# STM32.net
KiCad netlist of a schematic drawn in Altium Designer
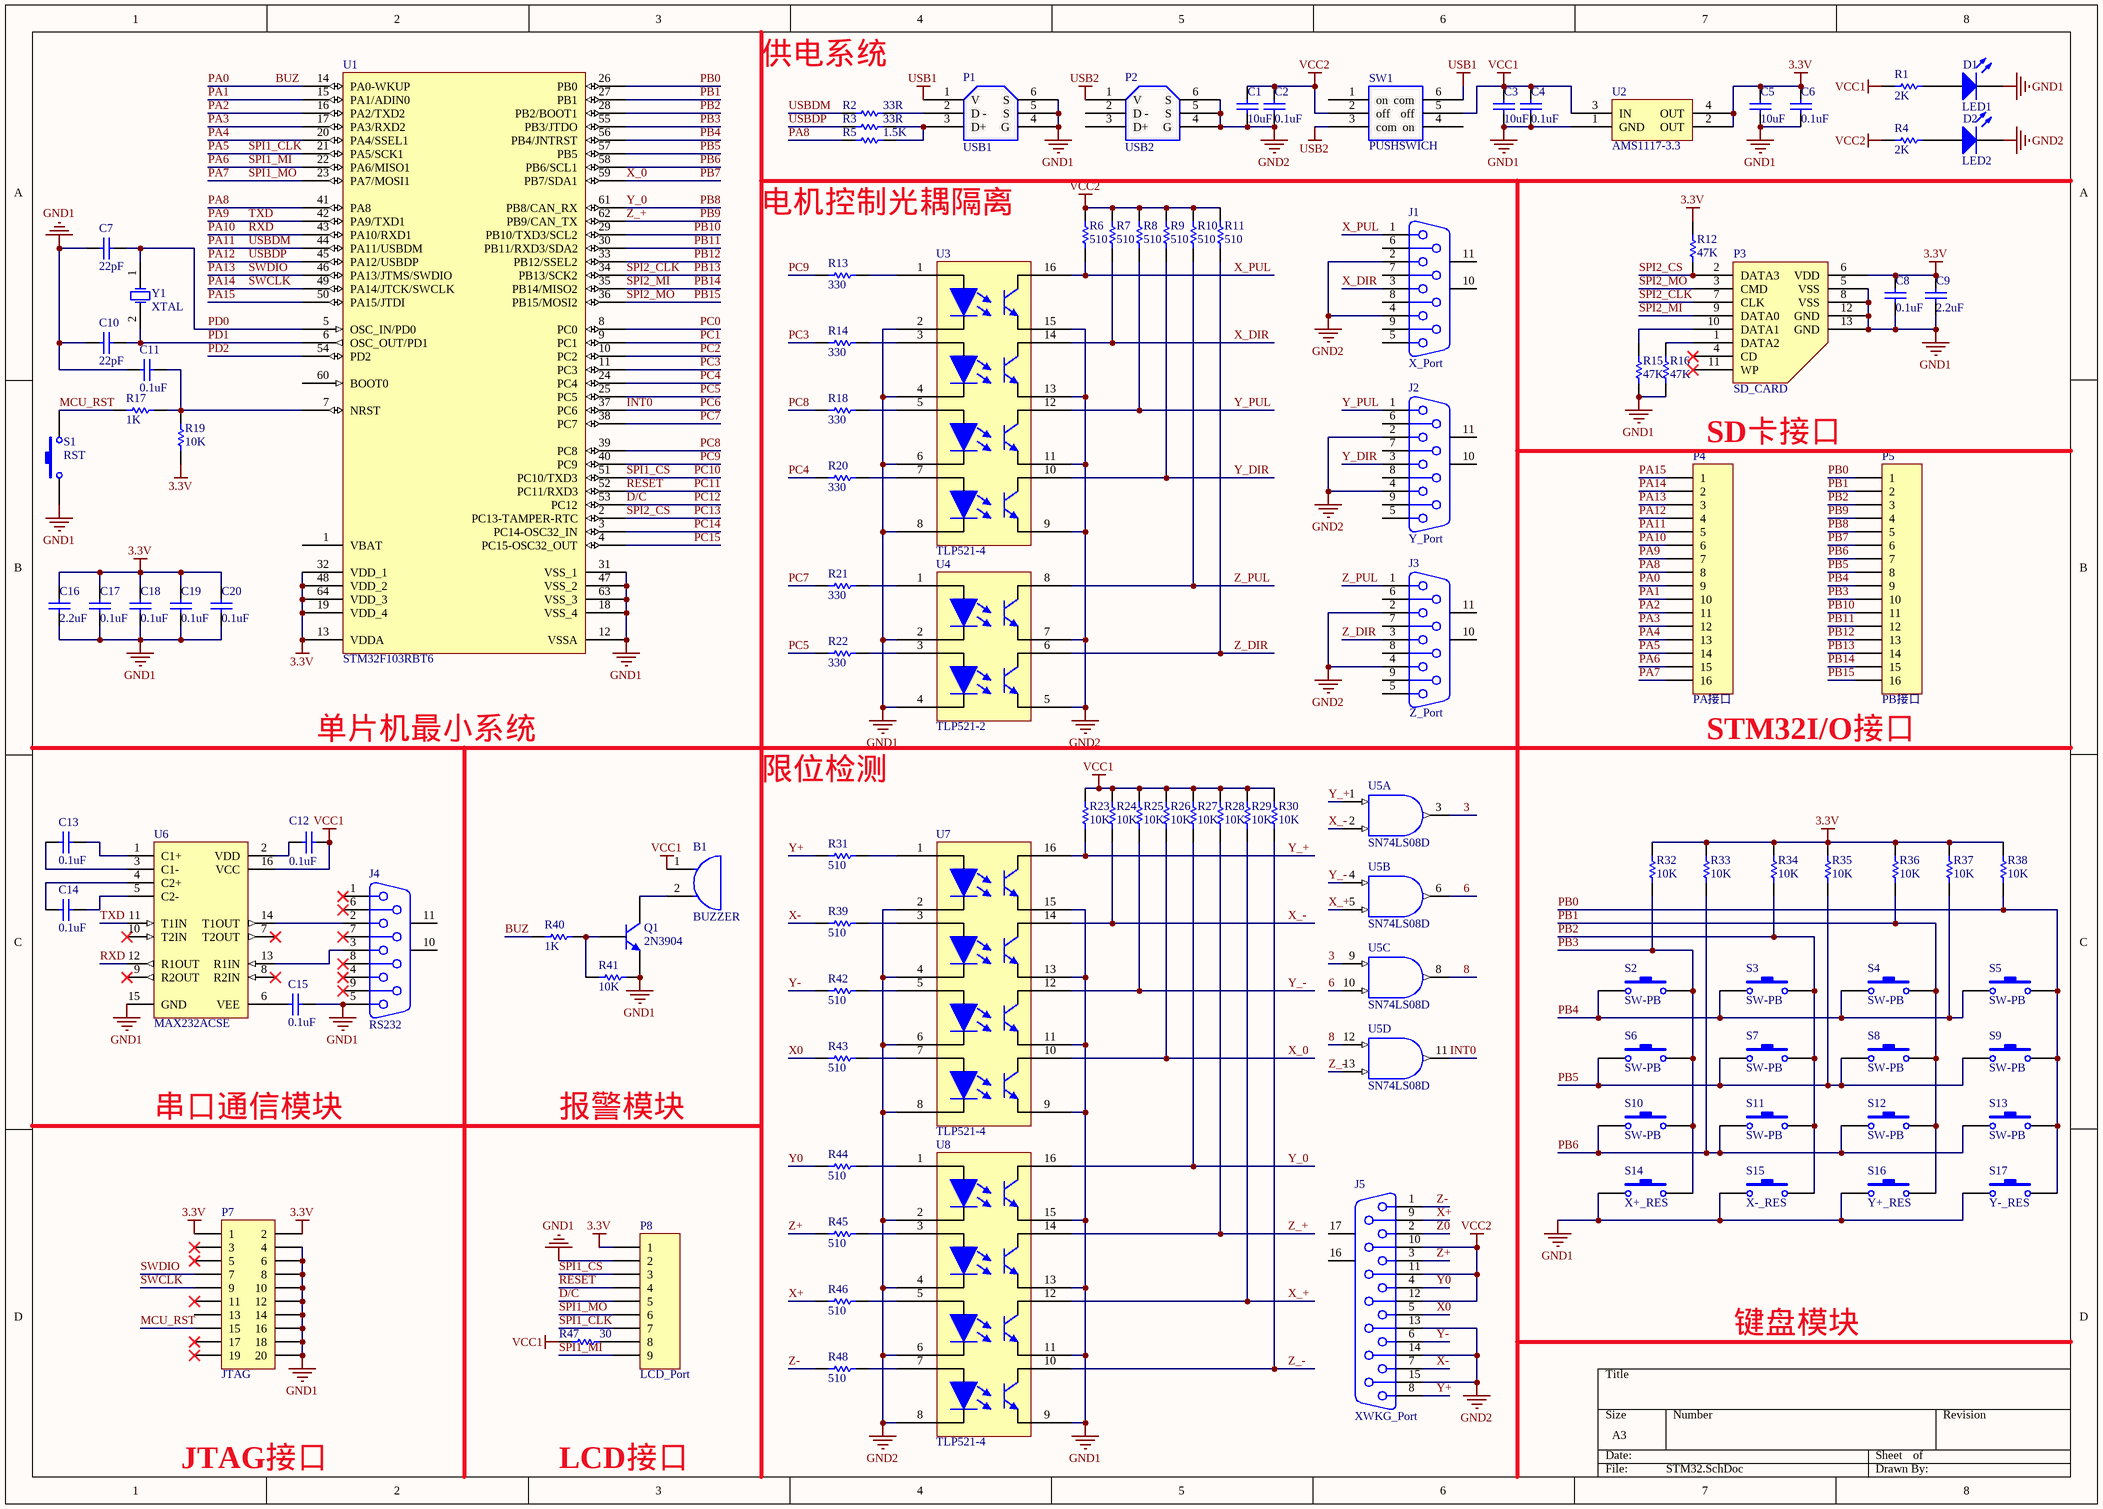
[diagram p0: STM32.SchDoc]

(export (version "E")
  (design (tool "Eeschema 10.0.6"))
  (components
    (comp (ref "B1")
      (value "BUZZER")
      (footprint "BUZZER")
      (description "Buzzer")
      (libsource (lib "Miscellaneous Devices") (part "BUZZER"))
    )
    (comp (ref "C1")
      (value "10uF")
      (footprint "0805")
      (description "Capacitor")
      (fields (field (name "Comment") "Cap") (field (name "PUBLISHER") "Altium Limited"))
      (libsource (lib "Miscellaneous Devices") (part "Cap"))
    )
    (comp (ref "C2")
      (value "0.1uF")
      (footprint "0805")
      (description "Capacitor")
      (fields (field (name "Comment") "Cap") (field (name "PUBLISHER") "Altium Limited"))
      (libsource (lib "Miscellaneous Devices") (part "Cap"))
    )
    (comp (ref "C3")
      (value "10uF")
      (footprint "0805")
      (description "Capacitor")
      (fields (field (name "Comment") "Cap") (field (name "PUBLISHER") "Altium Limited"))
      (libsource (lib "Miscellaneous Devices") (part "Cap"))
    )
    (comp (ref "C4")
      (value "0.1uF")
      (footprint "0805")
      (description "Capacitor")
      (fields (field (name "Comment") "Cap") (field (name "PUBLISHER") "Altium Limited"))
      (libsource (lib "Miscellaneous Devices") (part "Cap"))
    )
    (comp (ref "C5")
      (value "10uF")
      (footprint "0805")
      (description "Capacitor")
      (fields (field (name "Comment") "Cap") (field (name "PUBLISHER") "Altium Limited"))
      (libsource (lib "Miscellaneous Devices") (part "Cap"))
    )
    (comp (ref "C6")
      (value "0.1uF")
      (footprint "0805")
      (description "Capacitor")
      (fields (field (name "Comment") "Cap") (field (name "PUBLISHER") "Altium Limited"))
      (libsource (lib "Miscellaneous Devices") (part "Cap"))
    )
    (comp (ref "C7")
      (value "22pF")
      (footprint "0805")
      (description "Capacitor")
      (fields (field (name "Comment") "Cap") (field (name "PUBLISHER") "Altium Limited"))
      (libsource (lib "Miscellaneous Devices") (part "Cap"))
    )
    (comp (ref "C8")
      (value "0.1uF")
      (footprint "0805")
      (description "Capacitor")
      (fields (field (name "Comment") "Cap") (field (name "PUBLISHER") "Altium Limited"))
      (libsource (lib "Miscellaneous Devices") (part "Cap"))
    )
    (comp (ref "C9")
      (value "2.2uF")
      (footprint "0805")
      (description "Capacitor")
      (fields (field (name "Comment") "Cap") (field (name "PUBLISHER") "Altium Limited"))
      (libsource (lib "Miscellaneous Devices") (part "Cap"))
    )
    (comp (ref "C10")
      (value "22pF")
      (footprint "0805")
      (description "Capacitor")
      (fields (field (name "Comment") "Cap") (field (name "PUBLISHER") "Altium Limited"))
      (libsource (lib "Miscellaneous Devices") (part "Cap"))
    )
    (comp (ref "C11")
      (value "0.1uF")
      (footprint "0805")
      (description "Capacitor")
      (fields (field (name "Comment") "Cap") (field (name "PUBLISHER") "Altium Limited"))
      (libsource (lib "Miscellaneous Devices") (part "Cap"))
    )
    (comp (ref "C12")
      (value "0.1uF")
      (footprint "0805")
      (description "Capacitor")
      (fields (field (name "Comment") "Cap") (field (name "PUBLISHER") "Altium Limited"))
      (libsource (lib "Miscellaneous Devices") (part "Cap"))
    )
    (comp (ref "C13")
      (value "0.1uF")
      (footprint "0805")
      (description "Capacitor")
      (fields (field (name "Comment") "Cap") (field (name "PUBLISHER") "Altium Limited"))
      (libsource (lib "Miscellaneous Devices") (part "Cap"))
    )
    (comp (ref "C14")
      (value "0.1uF")
      (footprint "0805")
      (description "Capacitor")
      (fields (field (name "Comment") "Cap") (field (name "PUBLISHER") "Altium Limited"))
      (libsource (lib "Miscellaneous Devices") (part "Cap"))
    )
    (comp (ref "C15")
      (value "0.1uF")
      (footprint "0805")
      (description "Capacitor")
      (fields (field (name "Comment") "Cap") (field (name "PUBLISHER") "Altium Limited"))
      (libsource (lib "Miscellaneous Devices") (part "Cap"))
    )
    (comp (ref "C16")
      (value "2.2uF")
      (footprint "ShiPeng:0805")
      (description "Capacitor")
      (fields (field (name "Comment") "Cap") (field (name "PUBLISHER") "Altium Limited"))
      (libsource (lib "Miscellaneous Devices") (part "Cap"))
    )
    (comp (ref "C17")
      (value "0.1uF")
      (footprint "ShiPeng:0805")
      (description "Capacitor")
      (fields (field (name "Comment") "Cap") (field (name "PUBLISHER") "Altium Limited"))
      (libsource (lib "Miscellaneous Devices") (part "Cap"))
    )
    (comp (ref "C18")
      (value "0.1uF")
      (footprint "ShiPeng:0805")
      (description "Capacitor")
      (fields (field (name "Comment") "Cap") (field (name "PUBLISHER") "Altium Limited"))
      (libsource (lib "Miscellaneous Devices") (part "Cap"))
    )
    (comp (ref "C19")
      (value "0.1uF")
      (footprint "ShiPeng:0805")
      (description "Capacitor")
      (fields (field (name "Comment") "Cap") (field (name "PUBLISHER") "Altium Limited"))
      (libsource (lib "Miscellaneous Devices") (part "Cap"))
    )
    (comp (ref "C20")
      (value "0.1uF")
      (footprint "ShiPeng:0805")
      (description "Capacitor")
      (fields (field (name "Comment") "Cap") (field (name "PUBLISHER") "Altium Limited"))
      (libsource (lib "Miscellaneous Devices") (part "Cap"))
    )
    (comp (ref "D1")
      (value "LED1")
      (footprint "0805")
      (description "Typical INFRARED GaAs LED")
      (fields (field (name "PUBLISHER") "Altium Limited"))
      (libsource (lib "Miscellaneous Devices") (part "LED0"))
    )
    (comp (ref "D2")
      (value "LED2")
      (footprint "0805")
      (description "Typical INFRARED GaAs LED")
      (fields (field (name "PUBLISHER") "Altium Limited"))
      (libsource (lib "Miscellaneous Devices") (part "LED0"))
    )
    (comp (ref "J1")
      (value "X_Port")
      (footprint "DSUB1.385-2H9")
      (description "Receptacle Assembly, 9 Position, Right Angle")
      (fields (field (name "PUBLISHER") "Altium Limited"))
      (libsource (lib "Miscellaneous Connectors") (part "D Connector 9"))
    )
    (comp (ref "J2")
      (value "Y_Port")
      (footprint "DSUB1.385-2H9")
      (description "Receptacle Assembly, 9 Position, Right Angle")
      (fields (field (name "PUBLISHER") "Altium Limited"))
      (libsource (lib "Miscellaneous Connectors") (part "D Connector 9"))
    )
    (comp (ref "J3")
      (value "Z_Port")
      (footprint "DSUB1.385-2H9")
      (description "Receptacle Assembly, 9 Position, Right Angle")
      (fields (field (name "PUBLISHER") "Altium Limited"))
      (libsource (lib "Miscellaneous Connectors") (part "D Connector 9"))
    )
    (comp (ref "J4")
      (value "RS232")
      (footprint "DSUB1.385-2H9")
      (description "Receptacle Assembly, 9 Position, Right Angle")
      (fields (field (name "PUBLISHER") "Altium Limited"))
      (libsource (lib "Miscellaneous Connectors") (part "D Connector 9"))
    )
    (comp (ref "J5")
      (value "XWKG_Port")
      (footprint "DSUB1.385-2H15")
      (description "Receptacle Assembly, 15 Position, Right Angle")
      (fields (field (name "PUBLISHER") "Altium Limited"))
      (libsource (lib "Miscellaneous Connectors") (part "D Connector 15"))
    )
    (comp (ref "P1") (value "USB1") (footprint "ShiPeng:USB") (libsource (lib "*") (part "USB")))
    (comp (ref "P2") (value "USB2") (footprint "ShiPeng:USB") (libsource (lib "*") (part "USB")))
    (comp (ref "P3") (value "SD_CARD") (footprint "SD_CARD") (libsource (lib "ShiPeng") (part "SD_CARD")))
    (comp (ref "P4")
      (value "PA接口")
      (footprint "HDR1X16")
      (description "Header, 16-Pin")
      (fields (field (name "PUBLISHER") "Altium Limited"))
      (libsource (lib "Miscellaneous Connectors") (part "Header 16"))
    )
    (comp (ref "P5")
      (value "PB接口")
      (footprint "HDR1X16")
      (description "Header, 16-Pin")
      (fields (field (name "PUBLISHER") "Altium Limited"))
      (libsource (lib "Miscellaneous Connectors") (part "Header 16"))
    )
    (comp (ref "P7")
      (value "JTAG")
      (footprint "ShiPeng:JTAG")
      (description "Header, 10-Pin, Dual row")
      (fields (field (name "PUBLISHER") "Altium Limited"))
      (libsource (lib "Miscellaneous Connectors") (part "Header 10X2"))
    )
    (comp (ref "P8")
      (value "LCD_Port")
      (footprint "HDR1X9")
      (description "Header, 9-Pin")
      (fields (field (name "PUBLISHER") "Altium Limited"))
      (libsource (lib "Miscellaneous Connectors") (part "Header 9"))
    )
    (comp (ref "Q1")
      (value "2N3904")
      (footprint "TO-92A")
      (description "NPN General Purpose Amplifier")
      (fields (field (name "PUBLISHER") "Altium Limited"))
      (libsource (lib "Miscellaneous Devices") (part "2N3904"))
    )
    (comp (ref "R1")
      (value "2K")
      (footprint "0805")
      (description "Semiconductor Resistor")
      (fields (field (name "PUBLISHER") "Altium Limited"))
      (libsource (lib "Miscellaneous Devices") (part "Res Semi"))
    )
    (comp (ref "R2")
      (value "33R")
      (footprint "0805")
      (description "Semiconductor Resistor")
      (fields (field (name "PUBLISHER") "Altium Limited"))
      (libsource (lib "Miscellaneous Devices") (part "Res Semi"))
    )
    (comp (ref "R3")
      (value "33R")
      (footprint "0805")
      (description "Semiconductor Resistor")
      (fields (field (name "PUBLISHER") "Altium Limited"))
      (libsource (lib "Miscellaneous Devices") (part "Res Semi"))
    )
    (comp (ref "R4")
      (value "2K")
      (footprint "0805")
      (description "Semiconductor Resistor")
      (fields (field (name "PUBLISHER") "Altium Limited"))
      (libsource (lib "Miscellaneous Devices") (part "Res Semi"))
    )
    (comp (ref "R5")
      (value "1.5K")
      (footprint "0805")
      (description "Semiconductor Resistor")
      (fields (field (name "PUBLISHER") "Altium Limited"))
      (libsource (lib "Miscellaneous Devices") (part "Res Semi"))
    )
    (comp (ref "R6")
      (value "510")
      (footprint "0805")
      (description "Semiconductor Resistor")
      (fields (field (name "PUBLISHER") "Altium Limited"))
      (libsource (lib "Miscellaneous Devices") (part "Res Semi"))
    )
    (comp (ref "R7")
      (value "510")
      (footprint "ShiPeng:0805")
      (description "Semiconductor Resistor")
      (fields (field (name "PUBLISHER") "Altium Limited"))
      (libsource (lib "Miscellaneous Devices") (part "Res Semi"))
    )
    (comp (ref "R8")
      (value "510")
      (footprint "ShiPeng:0805")
      (description "Semiconductor Resistor")
      (fields (field (name "PUBLISHER") "Altium Limited"))
      (libsource (lib "Miscellaneous Devices") (part "Res Semi"))
    )
    (comp (ref "R9")
      (value "510")
      (footprint "ShiPeng:0805")
      (description "Semiconductor Resistor")
      (fields (field (name "PUBLISHER") "Altium Limited"))
      (libsource (lib "Miscellaneous Devices") (part "Res Semi"))
    )
    (comp (ref "R10")
      (value "510")
      (footprint "ShiPeng:0805")
      (description "Semiconductor Resistor")
      (fields (field (name "PUBLISHER") "Altium Limited"))
      (libsource (lib "Miscellaneous Devices") (part "Res Semi"))
    )
    (comp (ref "R11")
      (value "510")
      (footprint "ShiPeng:0805")
      (description "Semiconductor Resistor")
      (fields (field (name "PUBLISHER") "Altium Limited"))
      (libsource (lib "Miscellaneous Devices") (part "Res Semi"))
    )
    (comp (ref "R12")
      (value "47K")
      (footprint "0805")
      (description "Semiconductor Resistor")
      (fields (field (name "PUBLISHER") "Altium Limited"))
      (libsource (lib "Miscellaneous Devices") (part "Res Semi"))
    )
    (comp (ref "R13")
      (value "330")
      (footprint "ShiPeng:0805")
      (description "Semiconductor Resistor")
      (fields (field (name "PUBLISHER") "Altium Limited"))
      (libsource (lib "Miscellaneous Devices") (part "Res Semi"))
    )
    (comp (ref "R14")
      (value "330")
      (footprint "ShiPeng:0805")
      (description "Semiconductor Resistor")
      (fields (field (name "PUBLISHER") "Altium Limited"))
      (libsource (lib "Miscellaneous Devices") (part "Res Semi"))
    )
    (comp (ref "R15")
      (value "47K")
      (footprint "ShiPeng:0805")
      (description "Semiconductor Resistor")
      (fields (field (name "PUBLISHER") "Altium Limited"))
      (libsource (lib "Miscellaneous Devices") (part "Res Semi"))
    )
    (comp (ref "R16")
      (value "47K")
      (footprint "0805")
      (description "Semiconductor Resistor")
      (fields (field (name "PUBLISHER") "Altium Limited"))
      (libsource (lib "Miscellaneous Devices") (part "Res Semi"))
    )
    (comp (ref "R17")
      (value "1K")
      (footprint "ShiPeng:0805")
      (description "Semiconductor Resistor")
      (fields (field (name "PUBLISHER") "Altium Limited"))
      (libsource (lib "Miscellaneous Devices") (part "Res Semi"))
    )
    (comp (ref "R18")
      (value "330")
      (footprint "ShiPeng:0805")
      (description "Semiconductor Resistor")
      (fields (field (name "PUBLISHER") "Altium Limited"))
      (libsource (lib "Miscellaneous Devices") (part "Res Semi"))
    )
    (comp (ref "R19")
      (value "10K")
      (footprint "ShiPeng:0805")
      (description "Semiconductor Resistor")
      (fields (field (name "PUBLISHER") "Altium Limited"))
      (libsource (lib "Miscellaneous Devices") (part "Res Semi"))
    )
    (comp (ref "R20")
      (value "330")
      (footprint "ShiPeng:0805")
      (description "Semiconductor Resistor")
      (fields (field (name "PUBLISHER") "Altium Limited"))
      (libsource (lib "Miscellaneous Devices") (part "Res Semi"))
    )
    (comp (ref "R21")
      (value "330")
      (footprint "0805")
      (description "Semiconductor Resistor")
      (fields (field (name "PUBLISHER") "Altium Limited"))
      (libsource (lib "Miscellaneous Devices") (part "Res Semi"))
    )
    (comp (ref "R22")
      (value "330")
      (footprint "ShiPeng:0805")
      (description "Semiconductor Resistor")
      (fields (field (name "PUBLISHER") "Altium Limited"))
      (libsource (lib "Miscellaneous Devices") (part "Res Semi"))
    )
    (comp (ref "R23")
      (value "10K")
      (footprint "ShiPeng:0805")
      (description "Semiconductor Resistor")
      (fields (field (name "PUBLISHER") "Altium Limited"))
      (libsource (lib "Miscellaneous Devices") (part "Res Semi"))
    )
    (comp (ref "R24")
      (value "10K")
      (footprint "ShiPeng:0805")
      (description "Semiconductor Resistor")
      (fields (field (name "PUBLISHER") "Altium Limited"))
      (libsource (lib "Miscellaneous Devices") (part "Res Semi"))
    )
    (comp (ref "R25")
      (value "10K")
      (footprint "ShiPeng:0805")
      (description "Semiconductor Resistor")
      (fields (field (name "PUBLISHER") "Altium Limited"))
      (libsource (lib "Miscellaneous Devices") (part "Res Semi"))
    )
    (comp (ref "R26")
      (value "10K")
      (footprint "ShiPeng:0805")
      (description "Semiconductor Resistor")
      (fields (field (name "PUBLISHER") "Altium Limited"))
      (libsource (lib "Miscellaneous Devices") (part "Res Semi"))
    )
    (comp (ref "R27")
      (value "10K")
      (footprint "ShiPeng:0805")
      (description "Semiconductor Resistor")
      (fields (field (name "PUBLISHER") "Altium Limited"))
      (libsource (lib "Miscellaneous Devices") (part "Res Semi"))
    )
    (comp (ref "R28")
      (value "10K")
      (footprint "ShiPeng:0805")
      (description "Semiconductor Resistor")
      (fields (field (name "PUBLISHER") "Altium Limited"))
      (libsource (lib "Miscellaneous Devices") (part "Res Semi"))
    )
    (comp (ref "R29")
      (value "10K")
      (footprint "ShiPeng:0805")
      (description "Semiconductor Resistor")
      (fields (field (name "PUBLISHER") "Altium Limited"))
      (libsource (lib "Miscellaneous Devices") (part "Res Semi"))
    )
    (comp (ref "R30")
      (value "10K")
      (footprint "ShiPeng:0805")
      (description "Semiconductor Resistor")
      (fields (field (name "PUBLISHER") "Altium Limited"))
      (libsource (lib "Miscellaneous Devices") (part "Res Semi"))
    )
    (comp (ref "R31")
      (value "510")
      (footprint "ShiPeng:0805")
      (description "Semiconductor Resistor")
      (fields (field (name "PUBLISHER") "Altium Limited"))
      (libsource (lib "Miscellaneous Devices") (part "Res Semi"))
    )
    (comp (ref "R32")
      (value "10K")
      (footprint "ShiPeng:0805")
      (description "Semiconductor Resistor")
      (fields (field (name "PUBLISHER") "Altium Limited"))
      (libsource (lib "Miscellaneous Devices") (part "Res Semi"))
    )
    (comp (ref "R33")
      (value "10K")
      (footprint "ShiPeng:0805")
      (description "Semiconductor Resistor")
      (fields (field (name "PUBLISHER") "Altium Limited"))
      (libsource (lib "Miscellaneous Devices") (part "Res Semi"))
    )
    (comp (ref "R34")
      (value "10K")
      (footprint "ShiPeng:0805")
      (description "Semiconductor Resistor")
      (fields (field (name "PUBLISHER") "Altium Limited"))
      (libsource (lib "Miscellaneous Devices") (part "Res Semi"))
    )
    (comp (ref "R35")
      (value "10K")
      (footprint "0805")
      (description "Semiconductor Resistor")
      (fields (field (name "PUBLISHER") "Altium Limited"))
      (libsource (lib "Miscellaneous Devices") (part "Res Semi"))
    )
    (comp (ref "R36")
      (value "10K")
      (footprint "ShiPeng:0805")
      (description "Semiconductor Resistor")
      (fields (field (name "PUBLISHER") "Altium Limited"))
      (libsource (lib "Miscellaneous Devices") (part "Res Semi"))
    )
    (comp (ref "R37")
      (value "10K")
      (footprint "ShiPeng:0805")
      (description "Semiconductor Resistor")
      (fields (field (name "PUBLISHER") "Altium Limited"))
      (libsource (lib "Miscellaneous Devices") (part "Res Semi"))
    )
    (comp (ref "R38")
      (value "10K")
      (footprint "ShiPeng:0805")
      (description "Semiconductor Resistor")
      (fields (field (name "PUBLISHER") "Altium Limited"))
      (libsource (lib "Miscellaneous Devices") (part "Res Semi"))
    )
    (comp (ref "R39")
      (value "510")
      (footprint "ShiPeng:0805")
      (description "Semiconductor Resistor")
      (fields (field (name "PUBLISHER") "Altium Limited"))
      (libsource (lib "Miscellaneous Devices") (part "Res Semi"))
    )
    (comp (ref "R40")
      (value "1K")
      (footprint "ShiPeng:0805")
      (description "Semiconductor Resistor")
      (fields (field (name "PUBLISHER") "Altium Limited"))
      (libsource (lib "Miscellaneous Devices") (part "Res Semi"))
    )
    (comp (ref "R41")
      (value "10K")
      (footprint "ShiPeng:0805")
      (description "Semiconductor Resistor")
      (fields (field (name "PUBLISHER") "Altium Limited"))
      (libsource (lib "Miscellaneous Devices") (part "Res Semi"))
    )
    (comp (ref "R42")
      (value "510")
      (footprint "ShiPeng:0805")
      (description "Semiconductor Resistor")
      (fields (field (name "PUBLISHER") "Altium Limited"))
      (libsource (lib "Miscellaneous Devices") (part "Res Semi"))
    )
    (comp (ref "R43")
      (value "510")
      (footprint "ShiPeng:0805")
      (description "Semiconductor Resistor")
      (fields (field (name "PUBLISHER") "Altium Limited"))
      (libsource (lib "Miscellaneous Devices") (part "Res Semi"))
    )
    (comp (ref "R44")
      (value "510")
      (footprint "ShiPeng:0805")
      (description "Semiconductor Resistor")
      (fields (field (name "PUBLISHER") "Altium Limited"))
      (libsource (lib "Miscellaneous Devices") (part "Res Semi"))
    )
    (comp (ref "R45")
      (value "510")
      (footprint "ShiPeng:0805")
      (description "Semiconductor Resistor")
      (fields (field (name "PUBLISHER") "Altium Limited"))
      (libsource (lib "Miscellaneous Devices") (part "Res Semi"))
    )
    (comp (ref "R46")
      (value "510")
      (footprint "ShiPeng:0805")
      (description "Semiconductor Resistor")
      (fields (field (name "PUBLISHER") "Altium Limited"))
      (libsource (lib "Miscellaneous Devices") (part "Res Semi"))
    )
    (comp (ref "R47")
      (value "30")
      (footprint "ShiPeng:0805")
      (description "Semiconductor Resistor")
      (fields (field (name "PUBLISHER") "Altium Limited"))
      (libsource (lib "Miscellaneous Devices") (part "Res Semi"))
    )
    (comp (ref "R48")
      (value "510")
      (footprint "ShiPeng:0805")
      (description "Semiconductor Resistor")
      (fields (field (name "PUBLISHER") "Altium Limited"))
      (libsource (lib "Miscellaneous Devices") (part "Res Semi"))
    )
    (comp (ref "S1")
      (value "RST")
      (footprint "SW-PB")
      (description "Switch")
      (fields (field (name "PUBLISHER") "Altium Limited"))
      (libsource (lib "Miscellaneous Devices") (part "SW-PB"))
    )
    (comp (ref "S2")
      (value "SW-PB")
      (footprint "SW-PB")
      (description "Switch")
      (fields (field (name "PUBLISHER") "Altium Limited"))
      (libsource (lib "Miscellaneous Devices") (part "SW-PB"))
    )
    (comp (ref "S3")
      (value "SW-PB")
      (footprint "SW-PB")
      (description "Switch")
      (fields (field (name "PUBLISHER") "Altium Limited"))
      (libsource (lib "Miscellaneous Devices") (part "SW-PB"))
    )
    (comp (ref "S4")
      (value "SW-PB")
      (footprint "SW-PB")
      (description "Switch")
      (fields (field (name "PUBLISHER") "Altium Limited"))
      (libsource (lib "Miscellaneous Devices") (part "SW-PB"))
    )
    (comp (ref "S5")
      (value "SW-PB")
      (footprint "SW-PB")
      (description "Switch")
      (fields (field (name "PUBLISHER") "Altium Limited"))
      (libsource (lib "Miscellaneous Devices") (part "SW-PB"))
    )
    (comp (ref "S6")
      (value "SW-PB")
      (footprint "SW-PB")
      (description "Switch")
      (fields (field (name "PUBLISHER") "Altium Limited"))
      (libsource (lib "Miscellaneous Devices") (part "SW-PB"))
    )
    (comp (ref "S7")
      (value "SW-PB")
      (footprint "SW-PB")
      (description "Switch")
      (fields (field (name "PUBLISHER") "Altium Limited"))
      (libsource (lib "Miscellaneous Devices") (part "SW-PB"))
    )
    (comp (ref "S8")
      (value "SW-PB")
      (footprint "SW-PB")
      (description "Switch")
      (fields (field (name "PUBLISHER") "Altium Limited"))
      (libsource (lib "Miscellaneous Devices") (part "SW-PB"))
    )
    (comp (ref "S9")
      (value "SW-PB")
      (footprint "SW-PB")
      (description "Switch")
      (fields (field (name "PUBLISHER") "Altium Limited"))
      (libsource (lib "Miscellaneous Devices") (part "SW-PB"))
    )
    (comp (ref "S10")
      (value "SW-PB")
      (footprint "SW-PB")
      (description "Switch")
      (fields (field (name "PUBLISHER") "Altium Limited"))
      (libsource (lib "Miscellaneous Devices") (part "SW-PB"))
    )
    (comp (ref "S11")
      (value "SW-PB")
      (footprint "SW-PB")
      (description "Switch")
      (fields (field (name "PUBLISHER") "Altium Limited"))
      (libsource (lib "Miscellaneous Devices") (part "SW-PB"))
    )
    (comp (ref "S12")
      (value "SW-PB")
      (footprint "SW-PB")
      (description "Switch")
      (fields (field (name "PUBLISHER") "Altium Limited"))
      (libsource (lib "Miscellaneous Devices") (part "SW-PB"))
    )
    (comp (ref "S13")
      (value "SW-PB")
      (footprint "SW-PB")
      (description "Switch")
      (fields (field (name "PUBLISHER") "Altium Limited"))
      (libsource (lib "Miscellaneous Devices") (part "SW-PB"))
    )
    (comp (ref "S14")
      (value "X+_RES")
      (footprint "SW-PB")
      (description "Switch")
      (fields (field (name "PUBLISHER") "Altium Limited"))
      (libsource (lib "Miscellaneous Devices") (part "SW-PB"))
    )
    (comp (ref "S15")
      (value "X-_RES")
      (footprint "SW-PB")
      (description "Switch")
      (fields (field (name "PUBLISHER") "Altium Limited"))
      (libsource (lib "Miscellaneous Devices") (part "SW-PB"))
    )
    (comp (ref "S16")
      (value "Y+_RES")
      (footprint "SW-PB")
      (description "Switch")
      (fields (field (name "PUBLISHER") "Altium Limited"))
      (libsource (lib "Miscellaneous Devices") (part "SW-PB"))
    )
    (comp (ref "S17")
      (value "Y-_RES")
      (footprint "SW-PB")
      (description "Switch")
      (fields (field (name "PUBLISHER") "Altium Limited"))
      (libsource (lib "Miscellaneous Devices") (part "SW-PB"))
    )
    (comp (ref "SW1")
      (value "PUSHSWICH")
      (footprint "ShiPeng:DPDT-6")
      (libsource (lib "ShiPeng") (part "PUSHSWICH"))
    )
    (comp (ref "U1")
      (value "STM32F103RBT6")
      (footprint "ShiPeng:LQFP64_L")
      (libsource (lib "ShiPeng") (part "STM32F103RBT6"))
    )
    (comp (ref "U2")
      (value "AMS1117-3.3")
      (footprint "ShiPeng:SOT223")
      (libsource (lib "ShiPeng") (part "AMS1117-3.3"))
    )
    (comp (ref "U3")
      (value "TLP521-4")
      (footprint "Miscellaneous Devices:DIP-16")
      (libsource (lib "ShiPeng") (part "TLP521-4"))
    )
    (comp (ref "U4")
      (value "TLP521-2")
      (footprint "Miscellaneous Devices:DIP-8")
      (libsource (lib "ShiPeng") (part "TLP521-2"))
    )
    (comp (ref "U5")
      (value "SN74LS08D")
      (footprint "ShiPeng:D014_N")
      (description "Quadruple 2-Input Positive-AND Gate")
      (fields (field (name "PUBLISHER") "Altium Limited"))
      (libsource (lib "TI Logic Gate 2") (part "SN74LS08D"))
    )
    (comp (ref "U6")
      (value "MAX232ACSE")
      (footprint "NSO16_N")
      (description "+5V Powered, Multi-Channel RS-232 Driver/Receiver")
      (fields (field (name "PUBLISHER") "Altium Limited"))
      (libsource (lib "Maxim Communication Transceiver") (part "MAX232ACSE"))
    )
    (comp (ref "U7")
      (value "TLP521-4")
      (footprint "Miscellaneous Devices:DIP-16")
      (libsource (lib "ShiPeng") (part "TLP521-4"))
    )
    (comp (ref "U8")
      (value "TLP521-4")
      (footprint "Miscellaneous Devices:DIP-16")
      (libsource (lib "ShiPeng") (part "TLP521-4"))
    )
    (comp (ref "Y1")
      (value "XTAL")
      (footprint "ShiPeng:JZ")
      (description "Crystal Oscillator")
      (fields (field (name "PUBLISHER") "Altium Limited"))
      (libsource (lib "Miscellaneous Devices") (part "XTAL"))
    )
  )
  (nets
    (net (code "1") (name "/3") (class "Default")
      (node (ref "U5") (pin "3") (pinfunction "Y_3") (pintype "output"))
      (node (ref "U5") (pin "9") (pinfunction "A_9") (pintype "input"))
    )
    (net (code "2") (name "/6") (class "Default")
      (node (ref "U5") (pin "10") (pinfunction "B_10") (pintype "input"))
      (node (ref "U5") (pin "6") (pinfunction "Y_6") (pintype "output"))
    )
    (net (code "3") (name "/8") (class "Default")
      (node (ref "U5") (pin "12") (pinfunction "A_12") (pintype "input"))
      (node (ref "U5") (pin "8") (pinfunction "Y_8") (pintype "output"))
    )
    (net (code "4") (name "/BUZ") (class "Default")
      (node (ref "P4") (pin "9") (pinfunction "9_9") (pintype "passive"))
      (node (ref "R40") (pin "1") (pinfunction "1_1") (pintype "passive"))
      (node (ref "U1") (pin "14") (pinfunction "PA0-WKUP_14") (pintype "bidirectional"))
    )
    (net (code "5") (name "/D{slash}C") (class "Default")
      (node (ref "P8") (pin "5") (pinfunction "5_5") (pintype "passive"))
      (node (ref "U1") (pin "53") (pinfunction "PC12_53") (pintype "bidirectional"))
    )
    (net (code "6") (name "/INT0") (class "Default")
      (node (ref "U1") (pin "37") (pinfunction "PC6_37") (pintype "bidirectional"))
      (node (ref "U5") (pin "11") (pinfunction "Y_11") (pintype "output"))
    )
    (net (code "7") (name "/MCU_RST") (class "Default")
      (node (ref "P7") (pin "15") (pinfunction "15_15") (pintype "passive"))
      (node (ref "R17") (pin "2") (pinfunction "2_2") (pintype "passive"))
      (node (ref "S1") (pin "2") (pinfunction "2_2") (pintype "passive"))
    )
    (net (code "8") (name "/PA1") (class "Default")
      (node (ref "P4") (pin "10") (pinfunction "10_10") (pintype "passive"))
      (node (ref "U1") (pin "15") (pinfunction "PA1/ADIN0_15") (pintype "bidirectional"))
    )
    (net (code "9") (name "/PA2") (class "Default")
      (node (ref "P4") (pin "11") (pinfunction "11_11") (pintype "passive"))
      (node (ref "U1") (pin "16") (pinfunction "PA2/TXD2_16") (pintype "bidirectional"))
    )
    (net (code "10") (name "/PA3") (class "Default")
      (node (ref "P4") (pin "12") (pinfunction "12_12") (pintype "passive"))
      (node (ref "U1") (pin "17") (pinfunction "PA3/RXD2_17") (pintype "bidirectional"))
    )
    (net (code "11") (name "/PA4") (class "Default")
      (node (ref "P4") (pin "13") (pinfunction "13_13") (pintype "passive"))
      (node (ref "U1") (pin "20") (pinfunction "PA4/SSEL1_20") (pintype "bidirectional"))
    )
    (net (code "12") (name "/PA5") (class "Default")
      (node (ref "P4") (pin "14") (pinfunction "14_14") (pintype "passive"))
      (node (ref "P8") (pin "7") (pinfunction "7_7") (pintype "passive"))
      (node (ref "U1") (pin "21") (pinfunction "PA5/SCK1_21") (pintype "bidirectional"))
    )
    (net (code "13") (name "/PA6") (class "Default")
      (node (ref "P4") (pin "15") (pinfunction "15_15") (pintype "passive"))
      (node (ref "P8") (pin "9") (pinfunction "9_9") (pintype "passive"))
      (node (ref "U1") (pin "22") (pinfunction "PA6/MISO1_22") (pintype "bidirectional"))
    )
    (net (code "14") (name "/PA7") (class "Default")
      (node (ref "P4") (pin "16") (pinfunction "16_16") (pintype "passive"))
      (node (ref "P8") (pin "6") (pinfunction "6_6") (pintype "passive"))
      (node (ref "U1") (pin "23") (pinfunction "PA7/MOSI1_23") (pintype "bidirectional"))
    )
    (net (code "15") (name "/PA8") (class "Default")
      (node (ref "P4") (pin "8") (pinfunction "8_8") (pintype "passive"))
      (node (ref "R5") (pin "1") (pinfunction "1_1") (pintype "passive"))
      (node (ref "U1") (pin "41") (pinfunction "PA8_41") (pintype "bidirectional"))
    )
    (net (code "16") (name "/PA9") (class "Default")
      (node (ref "P4") (pin "7") (pinfunction "7_7") (pintype "passive"))
      (node (ref "U1") (pin "42") (pinfunction "PA9/TXD1_42") (pintype "bidirectional"))
      (node (ref "U6") (pin "11") (pinfunction "T1IN_11") (pintype "input"))
    )
    (net (code "17") (name "/PA10") (class "Default")
      (node (ref "P4") (pin "6") (pinfunction "6_6") (pintype "passive"))
      (node (ref "U1") (pin "43") (pinfunction "PA10/RXD1_43") (pintype "bidirectional"))
      (node (ref "U6") (pin "12") (pinfunction "R1OUT_12") (pintype "output"))
    )
    (net (code "18") (name "/PA11") (class "Default")
      (node (ref "P4") (pin "5") (pinfunction "5_5") (pintype "passive"))
      (node (ref "R2") (pin "1") (pinfunction "1_1") (pintype "passive"))
      (node (ref "U1") (pin "44") (pinfunction "PA11/USBDM_44") (pintype "bidirectional"))
    )
    (net (code "19") (name "/PA12") (class "Default")
      (node (ref "P4") (pin "4") (pinfunction "4_4") (pintype "passive"))
      (node (ref "R3") (pin "1") (pinfunction "1_1") (pintype "passive"))
      (node (ref "U1") (pin "45") (pinfunction "PA12/USBDP_45") (pintype "bidirectional"))
    )
    (net (code "20") (name "/PA13") (class "Default")
      (node (ref "P4") (pin "3") (pinfunction "3_3") (pintype "passive"))
      (node (ref "P7") (pin "7") (pinfunction "7_7") (pintype "passive"))
      (node (ref "U1") (pin "46") (pinfunction "PA13/JTMS/SWDIO_46") (pintype "bidirectional"))
    )
    (net (code "21") (name "/PA14") (class "Default")
      (node (ref "P4") (pin "2") (pinfunction "2_2") (pintype "passive"))
      (node (ref "P7") (pin "9") (pinfunction "9_9") (pintype "passive"))
      (node (ref "U1") (pin "49") (pinfunction "PA14/JTCK/SWCLK_49") (pintype "bidirectional"))
    )
    (net (code "22") (name "/PA15") (class "Default")
      (node (ref "P4") (pin "1") (pinfunction "1_1") (pintype "passive"))
      (node (ref "U1") (pin "50") (pinfunction "PA15/JTDI_50") (pintype "bidirectional"))
    )
    (net (code "23") (name "/PB0") (class "Default")
      (node (ref "P5") (pin "1") (pinfunction "1_1") (pintype "passive"))
      (node (ref "R38") (pin "2") (pinfunction "2_2") (pintype "passive"))
      (node (ref "S13") (pin "2") (pinfunction "2_2") (pintype "passive"))
      (node (ref "S17") (pin "2") (pinfunction "2_2") (pintype "passive"))
      (node (ref "S5") (pin "2") (pinfunction "2_2") (pintype "passive"))
      (node (ref "S9") (pin "2") (pinfunction "2_2") (pintype "passive"))
      (node (ref "U1") (pin "26") (pinfunction "PB0_26") (pintype "bidirectional"))
    )
    (net (code "24") (name "/PB1") (class "Default")
      (node (ref "P5") (pin "2") (pinfunction "2_2") (pintype "passive"))
      (node (ref "R36") (pin "2") (pinfunction "2_2") (pintype "passive"))
      (node (ref "S12") (pin "2") (pinfunction "2_2") (pintype "passive"))
      (node (ref "S16") (pin "2") (pinfunction "2_2") (pintype "passive"))
      (node (ref "S4") (pin "2") (pinfunction "2_2") (pintype "passive"))
      (node (ref "S8") (pin "2") (pinfunction "2_2") (pintype "passive"))
      (node (ref "U1") (pin "27") (pinfunction "PB1_27") (pintype "bidirectional"))
    )
    (net (code "25") (name "/PB2") (class "Default")
      (node (ref "P5") (pin "3") (pinfunction "3_3") (pintype "passive"))
      (node (ref "R34") (pin "2") (pinfunction "2_2") (pintype "passive"))
      (node (ref "S11") (pin "2") (pinfunction "2_2") (pintype "passive"))
      (node (ref "S15") (pin "2") (pinfunction "2_2") (pintype "passive"))
      (node (ref "S3") (pin "2") (pinfunction "2_2") (pintype "passive"))
      (node (ref "S7") (pin "2") (pinfunction "2_2") (pintype "passive"))
      (node (ref "U1") (pin "28") (pinfunction "PB2/BOOT1_28") (pintype "bidirectional"))
    )
    (net (code "26") (name "/PB3") (class "Default")
      (node (ref "P5") (pin "10") (pinfunction "10_10") (pintype "passive"))
      (node (ref "R32") (pin "2") (pinfunction "2_2") (pintype "passive"))
      (node (ref "S10") (pin "2") (pinfunction "2_2") (pintype "passive"))
      (node (ref "S14") (pin "2") (pinfunction "2_2") (pintype "passive"))
      (node (ref "S2") (pin "2") (pinfunction "2_2") (pintype "passive"))
      (node (ref "S6") (pin "2") (pinfunction "2_2") (pintype "passive"))
      (node (ref "U1") (pin "55") (pinfunction "PB3/JTDO_55") (pintype "bidirectional"))
    )
    (net (code "27") (name "/PB4") (class "Default")
      (node (ref "P5") (pin "9") (pinfunction "9_9") (pintype "passive"))
      (node (ref "R37") (pin "2") (pinfunction "2_2") (pintype "passive"))
      (node (ref "S2") (pin "1") (pinfunction "1_1") (pintype "passive"))
      (node (ref "S3") (pin "1") (pinfunction "1_1") (pintype "passive"))
      (node (ref "S4") (pin "1") (pinfunction "1_1") (pintype "passive"))
      (node (ref "S5") (pin "1") (pinfunction "1_1") (pintype "passive"))
      (node (ref "U1") (pin "56") (pinfunction "PB4/JNTRST_56") (pintype "bidirectional"))
    )
    (net (code "28") (name "/PB5") (class "Default")
      (node (ref "P5") (pin "8") (pinfunction "8_8") (pintype "passive"))
      (node (ref "R35") (pin "2") (pinfunction "2_2") (pintype "passive"))
      (node (ref "S6") (pin "1") (pinfunction "1_1") (pintype "passive"))
      (node (ref "S7") (pin "1") (pinfunction "1_1") (pintype "passive"))
      (node (ref "S8") (pin "1") (pinfunction "1_1") (pintype "passive"))
      (node (ref "S9") (pin "1") (pinfunction "1_1") (pintype "passive"))
      (node (ref "U1") (pin "57") (pinfunction "PB5_57") (pintype "bidirectional"))
    )
    (net (code "29") (name "/PB6") (class "Default")
      (node (ref "P5") (pin "7") (pinfunction "7_7") (pintype "passive"))
      (node (ref "R33") (pin "2") (pinfunction "2_2") (pintype "passive"))
      (node (ref "S10") (pin "1") (pinfunction "1_1") (pintype "passive"))
      (node (ref "S11") (pin "1") (pinfunction "1_1") (pintype "passive"))
      (node (ref "S12") (pin "1") (pinfunction "1_1") (pintype "passive"))
      (node (ref "S13") (pin "1") (pinfunction "1_1") (pintype "passive"))
      (node (ref "U1") (pin "58") (pinfunction "PB6/SCL1_58") (pintype "bidirectional"))
    )
    (net (code "30") (name "/PB7") (class "Default")
      (node (ref "P5") (pin "6") (pinfunction "6_6") (pintype "passive"))
      (node (ref "R26") (pin "2") (pinfunction "2_2") (pintype "passive"))
      (node (ref "U1") (pin "59") (pinfunction "PB7/SDA1_59") (pintype "bidirectional"))
      (node (ref "U7") (pin "10") (pintype "passive"))
    )
    (net (code "31") (name "/PB8") (class "Default")
      (node (ref "P5") (pin "5") (pinfunction "5_5") (pintype "passive"))
      (node (ref "R27") (pin "2") (pinfunction "2_2") (pintype "passive"))
      (node (ref "U1") (pin "61") (pinfunction "PB8/CAN_RX_61") (pintype "bidirectional"))
      (node (ref "U8") (pin "16") (pintype "passive"))
    )
    (net (code "32") (name "/PB9") (class "Default")
      (node (ref "P5") (pin "4") (pinfunction "4_4") (pintype "passive"))
      (node (ref "R28") (pin "2") (pinfunction "2_2") (pintype "passive"))
      (node (ref "U1") (pin "62") (pinfunction "PB9/CAN_TX_62") (pintype "bidirectional"))
      (node (ref "U8") (pin "14") (pintype "passive"))
    )
    (net (code "33") (name "/PB10") (class "Default")
      (node (ref "P5") (pin "11") (pinfunction "11_11") (pintype "passive"))
      (node (ref "U1") (pin "29") (pinfunction "PB10/TXD3/SCL2_29") (pintype "bidirectional"))
    )
    (net (code "34") (name "/PB11") (class "Default")
      (node (ref "P5") (pin "12") (pinfunction "12_12") (pintype "passive"))
      (node (ref "U1") (pin "30") (pinfunction "PB11/RXD3/SDA2_30") (pintype "bidirectional"))
    )
    (net (code "35") (name "/PB12") (class "Default")
      (node (ref "P5") (pin "13") (pinfunction "13_13") (pintype "passive"))
      (node (ref "U1") (pin "33") (pinfunction "PB12/SSEL2_33") (pintype "bidirectional"))
    )
    (net (code "36") (name "/PB13") (class "Default")
      (node (ref "P3") (pin "7") (pinfunction "CLK_7") (pintype "passive"))
      (node (ref "P5") (pin "14") (pinfunction "14_14") (pintype "passive"))
      (node (ref "U1") (pin "34") (pinfunction "PB13/SCK2_34") (pintype "bidirectional"))
    )
    (net (code "37") (name "/PB14") (class "Default")
      (node (ref "P3") (pin "9") (pinfunction "DATA0_9") (pintype "passive"))
      (node (ref "P5") (pin "15") (pinfunction "15_15") (pintype "passive"))
      (node (ref "U1") (pin "35") (pinfunction "PB14/MISO2_35") (pintype "bidirectional"))
    )
    (net (code "38") (name "/PB15") (class "Default")
      (node (ref "P3") (pin "3") (pinfunction "CMD_3") (pintype "passive"))
      (node (ref "P5") (pin "16") (pinfunction "16_16") (pintype "passive"))
      (node (ref "U1") (pin "36") (pinfunction "PB15/MOSI2_36") (pintype "bidirectional"))
    )
    (net (code "39") (name "/PC0") (class "Default")
      (node (ref "U1") (pin "8") (pinfunction "PC0_8") (pintype "bidirectional"))
    )
    (net (code "40") (name "/PC1") (class "Default")
      (node (ref "U1") (pin "9") (pinfunction "PC1_9") (pintype "bidirectional"))
    )
    (net (code "41") (name "/PC2") (class "Default")
      (node (ref "U1") (pin "10") (pinfunction "PC2_10") (pintype "bidirectional"))
    )
    (net (code "42") (name "/PC3") (class "Default")
      (node (ref "R14") (pin "2") (pinfunction "2_2") (pintype "passive"))
      (node (ref "U1") (pin "11") (pinfunction "PC3_11") (pintype "bidirectional"))
    )
    (net (code "43") (name "/PC4") (class "Default")
      (node (ref "R20") (pin "2") (pinfunction "2_2") (pintype "passive"))
      (node (ref "U1") (pin "24") (pinfunction "PC4_24") (pintype "bidirectional"))
    )
    (net (code "44") (name "/PC5") (class "Default")
      (node (ref "R22") (pin "2") (pinfunction "2_2") (pintype "passive"))
      (node (ref "U1") (pin "25") (pinfunction "PC5_25") (pintype "bidirectional"))
    )
    (net (code "45") (name "/PC7") (class "Default")
      (node (ref "R21") (pin "2") (pinfunction "2_2") (pintype "passive"))
      (node (ref "U1") (pin "38") (pinfunction "PC7_38") (pintype "bidirectional"))
    )
    (net (code "46") (name "/PC8") (class "Default")
      (node (ref "R18") (pin "2") (pinfunction "2_2") (pintype "passive"))
      (node (ref "U1") (pin "39") (pinfunction "PC8_39") (pintype "bidirectional"))
    )
    (net (code "47") (name "/PC9") (class "Default")
      (node (ref "R13") (pin "2") (pinfunction "2_2") (pintype "passive"))
      (node (ref "U1") (pin "40") (pinfunction "PC9_40") (pintype "bidirectional"))
    )
    (net (code "48") (name "/PC10") (class "Default")
      (node (ref "P8") (pin "3") (pinfunction "3_3") (pintype "passive"))
      (node (ref "U1") (pin "51") (pinfunction "PC10/TXD3_51") (pintype "bidirectional"))
    )
    (net (code "49") (name "/PC11") (class "Default")
      (node (ref "P8") (pin "4") (pinfunction "4_4") (pintype "passive"))
      (node (ref "U1") (pin "52") (pinfunction "PC11/RXD3_52") (pintype "bidirectional"))
    )
    (net (code "50") (name "/PC13") (class "Default")
      (node (ref "P3") (pin "2") (pinfunction "DATA3_2") (pintype "passive"))
      (node (ref "R12") (pin "1") (pinfunction "1_1") (pintype "passive"))
      (node (ref "U1") (pin "2") (pinfunction "PC13-TAMPER-RTC_2") (pintype "bidirectional"))
    )
    (net (code "51") (name "/PC14") (class "Default")
      (node (ref "U1") (pin "3") (pinfunction "PC14-OSC32_IN_3") (pintype "bidirectional"))
    )
    (net (code "52") (name "/PC15") (class "Default")
      (node (ref "U1") (pin "4") (pinfunction "PC15-OSC32_OUT_4") (pintype "bidirectional"))
    )
    (net (code "53") (name "/PD0") (class "Default")
      (node (ref "C7") (pin "2") (pinfunction "2_2") (pintype "passive"))
      (node (ref "U1") (pin "5") (pinfunction "OSC_IN/PD0_5") (pintype "input"))
      (node (ref "Y1") (pin "1") (pinfunction "OSC1_1") (pintype "passive"))
    )
    (net (code "54") (name "/PD1") (class "Default")
      (node (ref "C10") (pin "2") (pinfunction "2_2") (pintype "passive"))
      (node (ref "U1") (pin "6") (pinfunction "OSC_OUT/PD1_6") (pintype "output"))
      (node (ref "Y1") (pin "2") (pinfunction "OSC2_2") (pintype "passive"))
    )
    (net (code "55") (name "/PD2") (class "Default")
      (node (ref "U1") (pin "54") (pinfunction "PD2_54") (pintype "bidirectional"))
    )
    (net (code "56") (name "/X+") (class "Default")
      (node (ref "J5") (pin "9") (pinfunction "9_9") (pintype "passive"))
      (node (ref "R46") (pin "2") (pinfunction "2_2") (pintype "passive"))
    )
    (net (code "57") (name "/X-") (class "Default")
      (node (ref "J5") (pin "7") (pinfunction "7_7") (pintype "passive"))
      (node (ref "R39") (pin "2") (pinfunction "2_2") (pintype "passive"))
    )
    (net (code "58") (name "/X0") (class "Default")
      (node (ref "J5") (pin "5") (pinfunction "5_5") (pintype "passive"))
      (node (ref "R43") (pin "2") (pinfunction "2_2") (pintype "passive"))
    )
    (net (code "59") (name "/X_+") (class "Default")
      (node (ref "R29") (pin "2") (pinfunction "2_2") (pintype "passive"))
      (node (ref "U5") (pin "5") (pinfunction "B_5") (pintype "input"))
      (node (ref "U8") (pin "12") (pintype "passive"))
    )
    (net (code "60") (name "/X_-") (class "Default")
      (node (ref "R24") (pin "2") (pinfunction "2_2") (pintype "passive"))
      (node (ref "U5") (pin "2") (pinfunction "B_2") (pintype "input"))
      (node (ref "U7") (pin "14") (pintype "passive"))
    )
    (net (code "61") (name "/X_DIR") (class "Default")
      (node (ref "J1") (pin "3") (pinfunction "3_3") (pintype "passive"))
      (node (ref "R7") (pin "2") (pinfunction "2_2") (pintype "passive"))
      (node (ref "U3") (pin "14") (pintype "passive"))
    )
    (net (code "62") (name "/X_PUL") (class "Default")
      (node (ref "J1") (pin "1") (pinfunction "1_1") (pintype "passive"))
      (node (ref "R6") (pin "2") (pinfunction "2_2") (pintype "passive"))
      (node (ref "U3") (pin "16") (pintype "passive"))
    )
    (net (code "63") (name "/Y+") (class "Default")
      (node (ref "J5") (pin "8") (pinfunction "8_8") (pintype "passive"))
      (node (ref "R31") (pin "2") (pinfunction "2_2") (pintype "passive"))
    )
    (net (code "64") (name "/Y-") (class "Default")
      (node (ref "J5") (pin "6") (pinfunction "6_6") (pintype "passive"))
      (node (ref "R42") (pin "2") (pinfunction "2_2") (pintype "passive"))
    )
    (net (code "65") (name "/Y0") (class "Default")
      (node (ref "J5") (pin "4") (pinfunction "4_4") (pintype "passive"))
      (node (ref "R44") (pin "2") (pinfunction "2_2") (pintype "passive"))
    )
    (net (code "66") (name "/Y_+") (class "Default")
      (node (ref "R23") (pin "2") (pinfunction "2_2") (pintype "passive"))
      (node (ref "U5") (pin "1") (pinfunction "A_1") (pintype "input"))
      (node (ref "U7") (pin "16") (pintype "passive"))
    )
    (net (code "67") (name "/Y_-") (class "Default")
      (node (ref "R25") (pin "2") (pinfunction "2_2") (pintype "passive"))
      (node (ref "U5") (pin "4") (pinfunction "A_4") (pintype "input"))
      (node (ref "U7") (pin "12") (pintype "passive"))
    )
    (net (code "68") (name "/Y_DIR") (class "Default")
      (node (ref "J2") (pin "3") (pinfunction "3_3") (pintype "passive"))
      (node (ref "R9") (pin "2") (pinfunction "2_2") (pintype "passive"))
      (node (ref "U3") (pin "10") (pintype "passive"))
    )
    (net (code "69") (name "/Y_PUL") (class "Default")
      (node (ref "J2") (pin "1") (pinfunction "1_1") (pintype "passive"))
      (node (ref "R8") (pin "2") (pinfunction "2_2") (pintype "passive"))
      (node (ref "U3") (pin "12") (pintype "passive"))
    )
    (net (code "70") (name "/Z+") (class "Default")
      (node (ref "J5") (pin "3") (pinfunction "3_3") (pintype "passive"))
      (node (ref "R45") (pin "2") (pinfunction "2_2") (pintype "passive"))
    )
    (net (code "71") (name "/Z-") (class "Default")
      (node (ref "J5") (pin "1") (pinfunction "1_1") (pintype "passive"))
      (node (ref "R48") (pin "2") (pinfunction "2_2") (pintype "passive"))
    )
    (net (code "72") (name "/Z0") (class "Default")
      (node (ref "J5") (pin "2") (pinfunction "2_2") (pintype "passive"))
    )
    (net (code "73") (name "/Z_-") (class "Default")
      (node (ref "R30") (pin "2") (pinfunction "2_2") (pintype "passive"))
      (node (ref "U5") (pin "13") (pinfunction "B_13") (pintype "input"))
      (node (ref "U8") (pin "10") (pintype "passive"))
    )
    (net (code "74") (name "/Z_DIR") (class "Default")
      (node (ref "J3") (pin "3") (pinfunction "3_3") (pintype "passive"))
      (node (ref "R11") (pin "2") (pinfunction "2_2") (pintype "passive"))
      (node (ref "U4") (pin "6") (pintype "passive"))
    )
    (net (code "75") (name "/Z_PUL") (class "Default")
      (node (ref "J3") (pin "1") (pinfunction "1_1") (pintype "passive"))
      (node (ref "R10") (pin "2") (pinfunction "2_2") (pintype "passive"))
      (node (ref "U4") (pin "8") (pintype "passive"))
    )
    (net (code "76") (name "3.3V") (class "Default")
      (node (ref "C16") (pin "2") (pinfunction "2_2") (pintype "passive"))
      (node (ref "C17") (pin "2") (pinfunction "2_2") (pintype "passive"))
      (node (ref "C18") (pin "2") (pinfunction "2_2") (pintype "passive"))
      (node (ref "C19") (pin "2") (pinfunction "2_2") (pintype "passive"))
      (node (ref "C20") (pin "2") (pinfunction "2_2") (pintype "passive"))
      (node (ref "C5") (pin "2") (pinfunction "2_2") (pintype "passive"))
      (node (ref "C6") (pin "2") (pinfunction "2_2") (pintype "passive"))
      (node (ref "C8") (pin "2") (pinfunction "2_2") (pintype "passive"))
      (node (ref "C9") (pin "2") (pinfunction "2_2") (pintype "passive"))
      (node (ref "P3") (pin "6") (pinfunction "VDD_6") (pintype "passive"))
      (node (ref "P7") (pin "1") (pinfunction "1_1") (pintype "passive"))
      (node (ref "P7") (pin "2") (pinfunction "2_2") (pintype "passive"))
      (node (ref "P8") (pin "1") (pinfunction "1_1") (pintype "passive"))
      (node (ref "R12") (pin "2") (pinfunction "2_2") (pintype "passive"))
      (node (ref "R19") (pin "1") (pinfunction "1_1") (pintype "passive"))
      (node (ref "R32") (pin "1") (pinfunction "1_1") (pintype "passive"))
      (node (ref "R33") (pin "1") (pinfunction "1_1") (pintype "passive"))
      (node (ref "R34") (pin "1") (pinfunction "1_1") (pintype "passive"))
      (node (ref "R35") (pin "1") (pinfunction "1_1") (pintype "passive"))
      (node (ref "R36") (pin "1") (pinfunction "1_1") (pintype "passive"))
      (node (ref "R37") (pin "1") (pinfunction "1_1") (pintype "passive"))
      (node (ref "R38") (pin "1") (pinfunction "1_1") (pintype "passive"))
      (node (ref "U1") (pin "13") (pinfunction "VDDA_13") (pintype "power_in"))
      (node (ref "U1") (pin "19") (pinfunction "VDD_4_19") (pintype "power_in"))
      (node (ref "U1") (pin "32") (pinfunction "VDD_1_32") (pintype "power_in"))
      (node (ref "U1") (pin "48") (pinfunction "VDD_2_48") (pintype "power_in"))
      (node (ref "U1") (pin "64") (pinfunction "VDD_3_64") (pintype "power_in"))
      (node (ref "U2") (pin "2") (pinfunction "OUT_2") (pintype "passive"))
      (node (ref "U2") (pin "4") (pinfunction "OUT_4") (pintype "passive"))
    )
    (net (code "77") (name "GND") (class "Default")
      (node (ref "U5") (pin "7") (pinfunction "GND_7") (pintype "power_in"))
    )
    (net (code "78") (name "GND1") (class "Default")
      (node (ref "C10") (pin "1") (pinfunction "1_1") (pintype "passive"))
      (node (ref "C11") (pin "1") (pinfunction "1_1") (pintype "passive"))
      (node (ref "C15") (pin "2") (pinfunction "2_2") (pintype "passive"))
      (node (ref "C16") (pin "1") (pinfunction "1_1") (pintype "passive"))
      (node (ref "C17") (pin "1") (pinfunction "1_1") (pintype "passive"))
      (node (ref "C18") (pin "1") (pinfunction "1_1") (pintype "passive"))
      (node (ref "C19") (pin "1") (pinfunction "1_1") (pintype "passive"))
      (node (ref "C20") (pin "1") (pinfunction "1_1") (pintype "passive"))
      (node (ref "C3") (pin "1") (pinfunction "1_1") (pintype "passive"))
      (node (ref "C4") (pin "1") (pinfunction "1_1") (pintype "passive"))
      (node (ref "C5") (pin "1") (pinfunction "1_1") (pintype "passive"))
      (node (ref "C6") (pin "1") (pinfunction "1_1") (pintype "passive"))
      (node (ref "C7") (pin "1") (pinfunction "1_1") (pintype "passive"))
      (node (ref "C8") (pin "1") (pinfunction "1_1") (pintype "passive"))
      (node (ref "C9") (pin "1") (pinfunction "1_1") (pintype "passive"))
      (node (ref "D1") (pin "2") (pinfunction "K_2") (pintype "passive"))
      (node (ref "J4") (pin "5") (pinfunction "5_5") (pintype "passive"))
      (node (ref "P1") (pin "4") (pinfunction "G_4") (pintype "passive"))
      (node (ref "P1") (pin "5") (pinfunction "S_5") (pintype "passive"))
      (node (ref "P1") (pin "6") (pinfunction "S_6") (pintype "passive"))
      (node (ref "P3") (pin "12") (pinfunction "GND_12") (pintype "passive"))
      (node (ref "P3") (pin "13") (pinfunction "GND_13") (pintype "passive"))
      (node (ref "P3") (pin "5") (pinfunction "VSS_5") (pintype "passive"))
      (node (ref "P3") (pin "8") (pinfunction "VSS_8") (pintype "passive"))
      (node (ref "P7") (pin "10") (pinfunction "10_10") (pintype "passive"))
      (node (ref "P7") (pin "12") (pinfunction "12_12") (pintype "passive"))
      (node (ref "P7") (pin "14") (pinfunction "14_14") (pintype "passive"))
      (node (ref "P7") (pin "16") (pinfunction "16_16") (pintype "passive"))
      (node (ref "P7") (pin "18") (pinfunction "18_18") (pintype "passive"))
      (node (ref "P7") (pin "20") (pinfunction "20_20") (pintype "passive"))
      (node (ref "P7") (pin "4") (pinfunction "4_4") (pintype "passive"))
      (node (ref "P7") (pin "6") (pinfunction "6_6") (pintype "passive"))
      (node (ref "P7") (pin "8") (pinfunction "8_8") (pintype "passive"))
      (node (ref "P8") (pin "2") (pinfunction "2_2") (pintype "passive"))
      (node (ref "Q1") (pin "1") (pinfunction "E_1") (pintype "passive"))
      (node (ref "R15") (pin "1") (pinfunction "1_1") (pintype "passive"))
      (node (ref "R16") (pin "1") (pinfunction "1_1") (pintype "passive"))
      (node (ref "R41") (pin "1") (pinfunction "1_1") (pintype "passive"))
      (node (ref "S1") (pin "1") (pinfunction "1_1") (pintype "passive"))
      (node (ref "S14") (pin "1") (pinfunction "1_1") (pintype "passive"))
      (node (ref "S15") (pin "1") (pinfunction "1_1") (pintype "passive"))
      (node (ref "S16") (pin "1") (pinfunction "1_1") (pintype "passive"))
      (node (ref "S17") (pin "1") (pinfunction "1_1") (pintype "passive"))
      (node (ref "U1") (pin "12") (pinfunction "VSSA_12") (pintype "power_in"))
      (node (ref "U1") (pin "18") (pinfunction "VSS_4_18") (pintype "power_in"))
      (node (ref "U1") (pin "31") (pinfunction "VSS_1_31") (pintype "power_in"))
      (node (ref "U1") (pin "47") (pinfunction "VSS_2_47") (pintype "power_in"))
      (node (ref "U1") (pin "63") (pinfunction "VSS_3_63") (pintype "power_in"))
      (node (ref "U2") (pin "1") (pinfunction "GND_1") (pintype "passive"))
      (node (ref "U3") (pin "2") (pintype "passive"))
      (node (ref "U3") (pin "4") (pintype "passive"))
      (node (ref "U3") (pin "6") (pintype "passive"))
      (node (ref "U3") (pin "8") (pintype "passive"))
      (node (ref "U4") (pin "2") (pintype "passive"))
      (node (ref "U4") (pin "4") (pintype "passive"))
      (node (ref "U6") (pin "15") (pinfunction "GND_15") (pintype "power_in"))
      (node (ref "U7") (pin "11") (pintype "passive"))
      (node (ref "U7") (pin "13") (pintype "passive"))
      (node (ref "U7") (pin "15") (pintype "passive"))
      (node (ref "U7") (pin "9") (pintype "passive"))
      (node (ref "U8") (pin "11") (pintype "passive"))
      (node (ref "U8") (pin "13") (pintype "passive"))
      (node (ref "U8") (pin "15") (pintype "passive"))
      (node (ref "U8") (pin "9") (pintype "passive"))
    )
    (net (code "79") (name "GND2") (class "Default")
      (node (ref "C1") (pin "1") (pinfunction "1_1") (pintype "passive"))
      (node (ref "C2") (pin "1") (pinfunction "1_1") (pintype "passive"))
      (node (ref "D2") (pin "2") (pinfunction "K_2") (pintype "passive"))
      (node (ref "J1") (pin "2") (pinfunction "2_2") (pintype "passive"))
      (node (ref "J1") (pin "4") (pinfunction "4_4") (pintype "passive"))
      (node (ref "J2") (pin "2") (pinfunction "2_2") (pintype "passive"))
      (node (ref "J2") (pin "4") (pinfunction "4_4") (pintype "passive"))
      (node (ref "J3") (pin "2") (pinfunction "2_2") (pintype "passive"))
      (node (ref "J3") (pin "4") (pinfunction "4_4") (pintype "passive"))
      (node (ref "J5") (pin "13") (pinfunction "13_13") (pintype "passive"))
      (node (ref "J5") (pin "14") (pinfunction "14_14") (pintype "passive"))
      (node (ref "J5") (pin "15") (pinfunction "15_15") (pintype "passive"))
      (node (ref "P2") (pin "4") (pinfunction "G_4") (pintype "passive"))
      (node (ref "P2") (pin "5") (pinfunction "S_5") (pintype "passive"))
      (node (ref "P2") (pin "6") (pinfunction "S_6") (pintype "passive"))
      (node (ref "U3") (pin "11") (pintype "passive"))
      (node (ref "U3") (pin "13") (pintype "passive"))
      (node (ref "U3") (pin "15") (pintype "passive"))
      (node (ref "U3") (pin "9") (pintype "passive"))
      (node (ref "U4") (pin "5") (pintype "passive"))
      (node (ref "U4") (pin "7") (pintype "passive"))
      (node (ref "U7") (pin "2") (pintype "passive"))
      (node (ref "U7") (pin "4") (pintype "passive"))
      (node (ref "U7") (pin "6") (pintype "passive"))
      (node (ref "U7") (pin "8") (pintype "passive"))
      (node (ref "U8") (pin "2") (pintype "passive"))
      (node (ref "U8") (pin "4") (pintype "passive"))
      (node (ref "U8") (pin "6") (pintype "passive"))
      (node (ref "U8") (pin "8") (pintype "passive"))
    )
    (net (code "80") (name "Net-(B1-B)") (class "Default")
      (node (ref "B1") (pin "2") (pinfunction "B_2") (pintype "passive"))
      (node (ref "Q1") (pin "3") (pinfunction "C_3") (pintype "passive"))
    )
    (net (code "81") (name "Net-(D1-A)") (class "Default")
      (node (ref "D1") (pin "1") (pinfunction "A_1") (pintype "passive"))
      (node (ref "R1") (pin "2") (pinfunction "2_2") (pintype "passive"))
    )
    (net (code "82") (name "Net-(D2-A)") (class "Default")
      (node (ref "D2") (pin "1") (pinfunction "A_1") (pintype "passive"))
      (node (ref "R4") (pin "2") (pinfunction "2_2") (pintype "passive"))
    )
    (net (code "83") (name "Net-(P1-D+)") (class "Default")
      (node (ref "P1") (pin "3") (pinfunction "D+_3") (pintype "passive"))
      (node (ref "R3") (pin "2") (pinfunction "2_2") (pintype "passive"))
      (node (ref "R5") (pin "2") (pinfunction "2_2") (pintype "passive"))
    )
    (net (code "84") (name "Net-(P1-D_-)") (class "Default")
      (node (ref "P1") (pin "2") (pinfunction "D_-_2") (pintype "passive"))
      (node (ref "R2") (pin "2") (pinfunction "2_2") (pintype "passive"))
    )
    (net (code "85") (name "Net-(P3-DATA1)") (class "Default")
      (node (ref "P3") (pin "10") (pinfunction "DATA1_10") (pintype "passive"))
      (node (ref "R15") (pin "2") (pinfunction "2_2") (pintype "passive"))
    )
    (net (code "86") (name "Net-(P3-DATA2)") (class "Default")
      (node (ref "P3") (pin "1") (pinfunction "DATA2_1") (pintype "passive"))
      (node (ref "R16") (pin "2") (pinfunction "2_2") (pintype "passive"))
    )
    (net (code "87") (name "Net-(P8-Pad8)") (class "Default")
      (node (ref "P8") (pin "8") (pinfunction "8_8") (pintype "passive"))
      (node (ref "R47") (pin "2") (pinfunction "2_2") (pintype "passive"))
    )
    (net (code "88") (name "Net-(Q1-B)") (class "Default")
      (node (ref "Q1") (pin "2") (pinfunction "B_2") (pintype "passive"))
      (node (ref "R40") (pin "2") (pinfunction "2_2") (pintype "passive"))
      (node (ref "R41") (pin "2") (pinfunction "2_2") (pintype "passive"))
    )
    (net (code "89") (name "Net-(R13-Pad1)") (class "Default")
      (node (ref "R13") (pin "1") (pinfunction "1_1") (pintype "passive"))
      (node (ref "U3") (pin "1") (pintype "passive"))
    )
    (net (code "90") (name "Net-(R14-Pad1)") (class "Default")
      (node (ref "R14") (pin "1") (pinfunction "1_1") (pintype "passive"))
      (node (ref "U3") (pin "3") (pintype "passive"))
    )
    (net (code "91") (name "Net-(R18-Pad1)") (class "Default")
      (node (ref "R18") (pin "1") (pinfunction "1_1") (pintype "passive"))
      (node (ref "U3") (pin "5") (pintype "passive"))
    )
    (net (code "92") (name "Net-(R20-Pad1)") (class "Default")
      (node (ref "R20") (pin "1") (pinfunction "1_1") (pintype "passive"))
      (node (ref "U3") (pin "7") (pintype "passive"))
    )
    (net (code "93") (name "Net-(R21-Pad1)") (class "Default")
      (node (ref "R21") (pin "1") (pinfunction "1_1") (pintype "passive"))
      (node (ref "U4") (pin "1") (pintype "passive"))
    )
    (net (code "94") (name "Net-(R22-Pad1)") (class "Default")
      (node (ref "R22") (pin "1") (pinfunction "1_1") (pintype "passive"))
      (node (ref "U4") (pin "3") (pintype "passive"))
    )
    (net (code "95") (name "Net-(R31-Pad1)") (class "Default")
      (node (ref "R31") (pin "1") (pinfunction "1_1") (pintype "passive"))
      (node (ref "U7") (pin "1") (pintype "passive"))
    )
    (net (code "96") (name "Net-(R39-Pad1)") (class "Default")
      (node (ref "R39") (pin "1") (pinfunction "1_1") (pintype "passive"))
      (node (ref "U7") (pin "3") (pintype "passive"))
    )
    (net (code "97") (name "Net-(R42-Pad1)") (class "Default")
      (node (ref "R42") (pin "1") (pinfunction "1_1") (pintype "passive"))
      (node (ref "U7") (pin "5") (pintype "passive"))
    )
    (net (code "98") (name "Net-(R43-Pad1)") (class "Default")
      (node (ref "R43") (pin "1") (pinfunction "1_1") (pintype "passive"))
      (node (ref "U7") (pin "7") (pintype "passive"))
    )
    (net (code "99") (name "Net-(R44-Pad1)") (class "Default")
      (node (ref "R44") (pin "1") (pinfunction "1_1") (pintype "passive"))
      (node (ref "U8") (pin "1") (pintype "passive"))
    )
    (net (code "100") (name "Net-(R45-Pad1)") (class "Default")
      (node (ref "R45") (pin "1") (pinfunction "1_1") (pintype "passive"))
      (node (ref "U8") (pin "3") (pintype "passive"))
    )
    (net (code "101") (name "Net-(R46-Pad1)") (class "Default")
      (node (ref "R46") (pin "1") (pinfunction "1_1") (pintype "passive"))
      (node (ref "U8") (pin "5") (pintype "passive"))
    )
    (net (code "102") (name "Net-(R48-Pad1)") (class "Default")
      (node (ref "R48") (pin "1") (pinfunction "1_1") (pintype "passive"))
      (node (ref "U8") (pin "7") (pintype "passive"))
    )
    (net (code "103") (name "Net-(U1-NRST)") (class "Default")
      (node (ref "C11") (pin "2") (pinfunction "2_2") (pintype "passive"))
      (node (ref "R17") (pin "1") (pinfunction "1_1") (pintype "passive"))
      (node (ref "R19") (pin "2") (pinfunction "2_2") (pintype "passive"))
      (node (ref "U1") (pin "7") (pinfunction "NRST_7") (pintype "bidirectional"))
    )
    (net (code "104") (name "Net-(U6-C1+)") (class "Default")
      (node (ref "C13") (pin "2") (pinfunction "2_2") (pintype "passive"))
      (node (ref "U6") (pin "1") (pinfunction "C1+_1") (pintype "passive"))
    )
    (net (code "105") (name "Net-(U6-C1-)") (class "Default")
      (node (ref "C13") (pin "1") (pinfunction "1_1") (pintype "passive"))
      (node (ref "U6") (pin "3") (pinfunction "C1-_3") (pintype "passive"))
    )
    (net (code "106") (name "Net-(U6-C2+)") (class "Default")
      (node (ref "C14") (pin "1") (pinfunction "1_1") (pintype "passive"))
      (node (ref "U6") (pin "4") (pinfunction "C2+_4") (pintype "passive"))
    )
    (net (code "107") (name "Net-(U6-C2-)") (class "Default")
      (node (ref "C14") (pin "2") (pinfunction "2_2") (pintype "passive"))
      (node (ref "U6") (pin "5") (pinfunction "C2-_5") (pintype "passive"))
    )
    (net (code "108") (name "Net-(U6-R1IN)") (class "Default")
      (node (ref "J4") (pin "3") (pinfunction "3_3") (pintype "passive"))
      (node (ref "U6") (pin "13") (pinfunction "R1IN_13") (pintype "input"))
    )
    (net (code "109") (name "Net-(U6-T1OUT)") (class "Default")
      (node (ref "J4") (pin "2") (pinfunction "2_2") (pintype "passive"))
      (node (ref "U6") (pin "14") (pinfunction "T1OUT_14") (pintype "output"))
    )
    (net (code "110") (name "Net-(U6-VDD)") (class "Default")
      (node (ref "C12") (pin "1") (pinfunction "1_1") (pintype "passive"))
      (node (ref "U6") (pin "2") (pinfunction "VDD_2") (pintype "power_in"))
    )
    (net (code "111") (name "Net-(U6-VEE)") (class "Default")
      (node (ref "C15") (pin "1") (pinfunction "1_1") (pintype "passive"))
      (node (ref "U6") (pin "6") (pinfunction "VEE_6") (pintype "power_in"))
    )
    (net (code "112") (name "USB1") (class "Default")
      (node (ref "P1") (pin "1") (pinfunction "V_1") (pintype "passive"))
      (node (ref "SW1") (pin "6") (pinfunction "com_6") (pintype "passive"))
    )
    (net (code "113") (name "USB2") (class "Default")
      (node (ref "P2") (pin "1") (pinfunction "V_1") (pintype "passive"))
      (node (ref "SW1") (pin "3") (pinfunction "com_3") (pintype "passive"))
    )
    (net (code "114") (name "VCC") (class "Default")
      (node (ref "U5") (pin "14") (pinfunction "VCC_14") (pintype "power_in"))
    )
    (net (code "115") (name "VCC1") (class "Default")
      (node (ref "B1") (pin "1") (pinfunction "A_1") (pintype "passive"))
      (node (ref "C12") (pin "2") (pinfunction "2_2") (pintype "passive"))
      (node (ref "C3") (pin "2") (pinfunction "2_2") (pintype "passive"))
      (node (ref "C4") (pin "2") (pinfunction "2_2") (pintype "passive"))
      (node (ref "R1") (pin "1") (pinfunction "1_1") (pintype "passive"))
      (node (ref "R23") (pin "1") (pinfunction "1_1") (pintype "passive"))
      (node (ref "R24") (pin "1") (pinfunction "1_1") (pintype "passive"))
      (node (ref "R25") (pin "1") (pinfunction "1_1") (pintype "passive"))
      (node (ref "R26") (pin "1") (pinfunction "1_1") (pintype "passive"))
      (node (ref "R27") (pin "1") (pinfunction "1_1") (pintype "passive"))
      (node (ref "R28") (pin "1") (pinfunction "1_1") (pintype "passive"))
      (node (ref "R29") (pin "1") (pinfunction "1_1") (pintype "passive"))
      (node (ref "R30") (pin "1") (pinfunction "1_1") (pintype "passive"))
      (node (ref "R47") (pin "1") (pinfunction "1_1") (pintype "passive"))
      (node (ref "SW1") (pin "5") (pinfunction "off_5") (pintype "passive"))
      (node (ref "U2") (pin "3") (pinfunction "IN_3") (pintype "passive"))
      (node (ref "U6") (pin "16") (pinfunction "VCC_16") (pintype "power_in"))
    )
    (net (code "116") (name "VCC2") (class "Default")
      (node (ref "C1") (pin "2") (pinfunction "2_2") (pintype "passive"))
      (node (ref "C2") (pin "2") (pinfunction "2_2") (pintype "passive"))
      (node (ref "J5") (pin "10") (pinfunction "10_10") (pintype "passive"))
      (node (ref "J5") (pin "11") (pinfunction "11_11") (pintype "passive"))
      (node (ref "J5") (pin "12") (pinfunction "12_12") (pintype "passive"))
      (node (ref "R10") (pin "1") (pinfunction "1_1") (pintype "passive"))
      (node (ref "R11") (pin "1") (pinfunction "1_1") (pintype "passive"))
      (node (ref "R4") (pin "1") (pinfunction "1_1") (pintype "passive"))
      (node (ref "R6") (pin "1") (pinfunction "1_1") (pintype "passive"))
      (node (ref "R7") (pin "1") (pinfunction "1_1") (pintype "passive"))
      (node (ref "R8") (pin "1") (pinfunction "1_1") (pintype "passive"))
      (node (ref "R9") (pin "1") (pinfunction "1_1") (pintype "passive"))
      (node (ref "SW1") (pin "2") (pinfunction "off_2") (pintype "passive"))
    )
    (net (code "117") (name "unconnected-(J1-MH1-Pad10)") (class "Default")
      (node (ref "J1") (pin "10") (pinfunction "MH1_10") (pintype "passive"))
    )
    (net (code "118") (name "unconnected-(J1-MH2-Pad11)") (class "Default")
      (node (ref "J1") (pin "11") (pinfunction "MH2_11") (pintype "passive"))
    )
    (net (code "119") (name "unconnected-(J1-Pad5)") (class "Default")
      (node (ref "J1") (pin "5") (pinfunction "5_5") (pintype "passive"))
    )
    (net (code "120") (name "unconnected-(J1-Pad6)") (class "Default")
      (node (ref "J1") (pin "6") (pinfunction "6_6") (pintype "passive"))
    )
    (net (code "121") (name "unconnected-(J1-Pad7)") (class "Default")
      (node (ref "J1") (pin "7") (pinfunction "7_7") (pintype "passive"))
    )
    (net (code "122") (name "unconnected-(J1-Pad8)") (class "Default")
      (node (ref "J1") (pin "8") (pinfunction "8_8") (pintype "passive"))
    )
    (net (code "123") (name "unconnected-(J1-Pad9)") (class "Default")
      (node (ref "J1") (pin "9") (pinfunction "9_9") (pintype "passive"))
    )
    (net (code "124") (name "unconnected-(J2-MH1-Pad10)") (class "Default")
      (node (ref "J2") (pin "10") (pinfunction "MH1_10") (pintype "passive"))
    )
    (net (code "125") (name "unconnected-(J2-MH2-Pad11)") (class "Default")
      (node (ref "J2") (pin "11") (pinfunction "MH2_11") (pintype "passive"))
    )
    (net (code "126") (name "unconnected-(J2-Pad5)") (class "Default")
      (node (ref "J2") (pin "5") (pinfunction "5_5") (pintype "passive"))
    )
    (net (code "127") (name "unconnected-(J2-Pad6)") (class "Default")
      (node (ref "J2") (pin "6") (pinfunction "6_6") (pintype "passive"))
    )
    (net (code "128") (name "unconnected-(J2-Pad7)") (class "Default")
      (node (ref "J2") (pin "7") (pinfunction "7_7") (pintype "passive"))
    )
    (net (code "129") (name "unconnected-(J2-Pad8)") (class "Default")
      (node (ref "J2") (pin "8") (pinfunction "8_8") (pintype "passive"))
    )
    (net (code "130") (name "unconnected-(J2-Pad9)") (class "Default")
      (node (ref "J2") (pin "9") (pinfunction "9_9") (pintype "passive"))
    )
    (net (code "131") (name "unconnected-(J3-MH1-Pad10)") (class "Default")
      (node (ref "J3") (pin "10") (pinfunction "MH1_10") (pintype "passive"))
    )
    (net (code "132") (name "unconnected-(J3-MH2-Pad11)") (class "Default")
      (node (ref "J3") (pin "11") (pinfunction "MH2_11") (pintype "passive"))
    )
    (net (code "133") (name "unconnected-(J3-Pad5)") (class "Default")
      (node (ref "J3") (pin "5") (pinfunction "5_5") (pintype "passive"))
    )
    (net (code "134") (name "unconnected-(J3-Pad6)") (class "Default")
      (node (ref "J3") (pin "6") (pinfunction "6_6") (pintype "passive"))
    )
    (net (code "135") (name "unconnected-(J3-Pad7)") (class "Default")
      (node (ref "J3") (pin "7") (pinfunction "7_7") (pintype "passive"))
    )
    (net (code "136") (name "unconnected-(J3-Pad8)") (class "Default")
      (node (ref "J3") (pin "8") (pinfunction "8_8") (pintype "passive"))
    )
    (net (code "137") (name "unconnected-(J3-Pad9)") (class "Default")
      (node (ref "J3") (pin "9") (pinfunction "9_9") (pintype "passive"))
    )
    (net (code "138") (name "unconnected-(J4-MH1-Pad10)") (class "Default")
      (node (ref "J4") (pin "10") (pinfunction "MH1_10") (pintype "passive"))
    )
    (net (code "139") (name "unconnected-(J4-MH2-Pad11)") (class "Default")
      (node (ref "J4") (pin "11") (pinfunction "MH2_11") (pintype "passive"))
    )
    (net (code "140") (name "unconnected-(J4-Pad1)") (class "Default")
      (node (ref "J4") (pin "1") (pinfunction "1_1") (pintype "passive+no_connect"))
    )
    (net (code "141") (name "unconnected-(J4-Pad4)") (class "Default")
      (node (ref "J4") (pin "4") (pinfunction "4_4") (pintype "passive+no_connect"))
    )
    (net (code "142") (name "unconnected-(J4-Pad6)") (class "Default")
      (node (ref "J4") (pin "6") (pinfunction "6_6") (pintype "passive+no_connect"))
    )
    (net (code "143") (name "unconnected-(J4-Pad7)") (class "Default")
      (node (ref "J4") (pin "7") (pinfunction "7_7") (pintype "passive+no_connect"))
    )
    (net (code "144") (name "unconnected-(J4-Pad8)") (class "Default")
      (node (ref "J4") (pin "8") (pinfunction "8_8") (pintype "passive+no_connect"))
    )
    (net (code "145") (name "unconnected-(J4-Pad9)") (class "Default")
      (node (ref "J4") (pin "9") (pinfunction "9_9") (pintype "passive+no_connect"))
    )
    (net (code "146") (name "unconnected-(J5-MH1-Pad16)") (class "Default")
      (node (ref "J5") (pin "16") (pinfunction "MH1_16") (pintype "passive"))
    )
    (net (code "147") (name "unconnected-(J5-MH2-Pad17)") (class "Default")
      (node (ref "J5") (pin "17") (pinfunction "MH2_17") (pintype "passive"))
    )
    (net (code "148") (name "unconnected-(P2-D+-Pad3)") (class "Default")
      (node (ref "P2") (pin "3") (pinfunction "D+_3") (pintype "passive"))
    )
    (net (code "149") (name "unconnected-(P2-D_--Pad2)") (class "Default")
      (node (ref "P2") (pin "2") (pinfunction "D_-_2") (pintype "passive"))
    )
    (net (code "150") (name "unconnected-(P3-CD-Pad4)") (class "Default")
      (node (ref "P3") (pin "4") (pinfunction "CD_4") (pintype "passive+no_connect"))
    )
    (net (code "151") (name "unconnected-(P3-WP-Pad11)") (class "Default")
      (node (ref "P3") (pin "11") (pinfunction "WP_11") (pintype "passive+no_connect"))
    )
    (net (code "152") (name "unconnected-(P7-Pad3)") (class "Default")
      (node (ref "P7") (pin "3") (pinfunction "3_3") (pintype "passive+no_connect"))
    )
    (net (code "153") (name "unconnected-(P7-Pad5)") (class "Default")
      (node (ref "P7") (pin "5") (pinfunction "5_5") (pintype "passive+no_connect"))
    )
    (net (code "154") (name "unconnected-(P7-Pad11)") (class "Default")
      (node (ref "P7") (pin "11") (pinfunction "11_11") (pintype "passive+no_connect"))
    )
    (net (code "155") (name "unconnected-(P7-Pad13)") (class "Default")
      (node (ref "P7") (pin "13") (pinfunction "13_13") (pintype "passive"))
    )
    (net (code "156") (name "unconnected-(P7-Pad17)") (class "Default")
      (node (ref "P7") (pin "17") (pinfunction "17_17") (pintype "passive+no_connect"))
    )
    (net (code "157") (name "unconnected-(P7-Pad19)") (class "Default")
      (node (ref "P7") (pin "19") (pinfunction "19_19") (pintype "passive+no_connect"))
    )
    (net (code "158") (name "unconnected-(SW1-on-Pad1)") (class "Default")
      (node (ref "SW1") (pin "1") (pinfunction "on_1") (pintype "passive"))
    )
    (net (code "159") (name "unconnected-(SW1-on-Pad4)") (class "Default")
      (node (ref "SW1") (pin "4") (pinfunction "on_4") (pintype "passive"))
    )
    (net (code "160") (name "unconnected-(U1-BOOT0-Pad60)") (class "Default")
      (node (ref "U1") (pin "60") (pinfunction "BOOT0_60") (pintype "input"))
    )
    (net (code "161") (name "unconnected-(U1-VBAT-Pad1)") (class "Default")
      (node (ref "U1") (pin "1") (pinfunction "VBAT_1") (pintype "power_in"))
    )
    (net (code "162") (name "unconnected-(U6-R2IN-Pad8)") (class "Default")
      (node (ref "U6") (pin "8") (pinfunction "R2IN_8") (pintype "input+no_connect"))
    )
    (net (code "163") (name "unconnected-(U6-R2OUT-Pad9)") (class "Default")
      (node (ref "U6") (pin "9") (pinfunction "R2OUT_9") (pintype "output+no_connect"))
    )
    (net (code "164") (name "unconnected-(U6-T2IN-Pad10)") (class "Default")
      (node (ref "U6") (pin "10") (pinfunction "T2IN_10") (pintype "input+no_connect"))
    )
    (net (code "165") (name "unconnected-(U6-T2OUT-Pad7)") (class "Default")
      (node (ref "U6") (pin "7") (pinfunction "T2OUT_7") (pintype "output+no_connect"))
    )
  )
)
